# PowerRailJumper.net
KiCad netlist of a schematic drawn in EAGLE
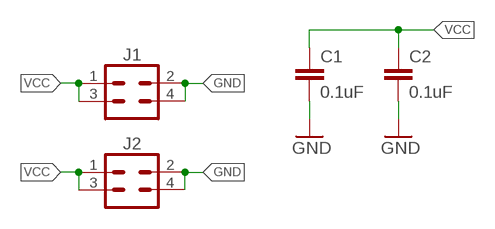
[diagram p0: schematic, sheet 1]

(export (version "E")
  (design (tool "Eeschema 10.0.6"))
  (components
    (comp (ref "C1")
      (value "0.1uF")
      (footprint "eagle-import:C0603")
      (fields (field (name "MF") "Murata") (field (name "MPN") "GCM188R71E104KA57D"))
      (libsource (lib "eagle-import") (part "C-EUC06030.1UF"))
    )
    (comp (ref "C2")
      (value "0.1uF")
      (footprint "eagle-import:C0603")
      (fields (field (name "MF") "Murata") (field (name "MPN") "GCM188R71E104KA57D"))
      (libsource (lib "eagle-import") (part "C-EUC06030.1UF"))
    )
    (comp (ref "J1")
      (value "CONN_2X2")
      (footprint "eagle-import:2X02")
      (libsource (lib "eagle-import") (part "CONN_2X2"))
    )
    (comp (ref "J2")
      (value "CONN_2X2")
      (footprint "eagle-import:2X02")
      (libsource (lib "eagle-import") (part "CONN_2X2"))
    )
  )
  (nets
    (net (code "1") (name "GND") (class "Default")
      (node (ref "C1") (pin "2") (pinfunction "2_2") (pintype "passive"))
      (node (ref "C2") (pin "2") (pinfunction "2_2") (pintype "passive"))
      (node (ref "J1") (pin "2") (pinfunction "2_2") (pintype "bidirectional"))
      (node (ref "J1") (pin "4") (pinfunction "4_4") (pintype "bidirectional"))
      (node (ref "J2") (pin "2") (pinfunction "2_2") (pintype "bidirectional"))
      (node (ref "J2") (pin "4") (pinfunction "4_4") (pintype "bidirectional"))
    )
    (net (code "2") (name "VCC") (class "Default")
      (node (ref "C1") (pin "1") (pinfunction "1_1") (pintype "passive"))
      (node (ref "C2") (pin "1") (pinfunction "1_1") (pintype "passive"))
      (node (ref "J1") (pin "1") (pinfunction "1_1") (pintype "bidirectional"))
      (node (ref "J1") (pin "3") (pinfunction "3_3") (pintype "bidirectional"))
      (node (ref "J2") (pin "1") (pinfunction "1_1") (pintype "bidirectional"))
      (node (ref "J2") (pin "3") (pinfunction "3_3") (pintype "bidirectional"))
    )
  )
)
